# USB.net
KiCad netlist of a schematic drawn in Altium Designer
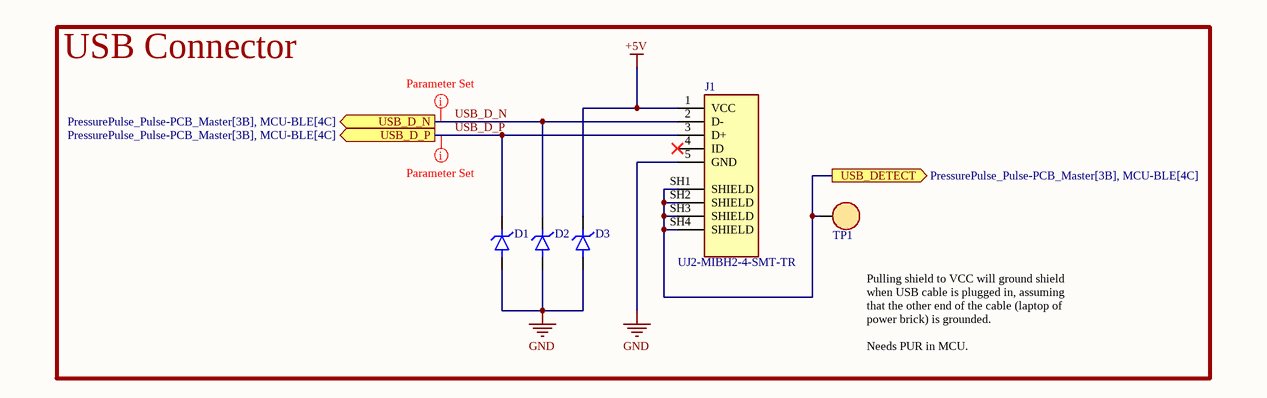
[diagram p0: USB.SchDoc]

(export (version "E")
  (design (tool "Eeschema 10.0.6"))
  (components
    (comp (ref "D1")
      (value "RCLAMP0521P.TCT")
      (footprint "PressurePulse:BDFN2C051V40")
      (description "25V Clamp 4A (8/20µs) Ipp Tvs Diode Surface Mount SLP1006P2")
      (fields (field (name "MFR") "BORN"))
      (libsource (lib "PressurePulse") (part "TVS DIODE"))
    )
    (comp (ref "D2")
      (value "RCLAMP0521P.TCT")
      (footprint "PressurePulse:BDFN2C051V40")
      (description "25V Clamp 4A (8/20µs) Ipp Tvs Diode Surface Mount SLP1006P2")
      (fields (field (name "MFR") "BORN"))
      (libsource (lib "PressurePulse") (part "TVS DIODE"))
    )
    (comp (ref "D3")
      (value "RCLAMP0521P.TCT")
      (footprint "PressurePulse:BDFN2C051V40")
      (description "25V Clamp 4A (8/20µs) Ipp Tvs Diode Surface Mount SLP1006P2")
      (fields (field (name "MFR") "BORN"))
      (libsource (lib "PressurePulse") (part "TVS DIODE"))
    )
    (comp (ref "J1")
      (value "UJ2-MIBH2-4-SMT-TR")
      (footprint "PressurePulse:USB MICRO JLC")
      (description "Micro B, USB 2.0, 1.8 A, Right Angle, Surface Mount (SMT), USB Receptacle")
      (fields (field (name "MFR") "CUI Devices"))
      (libsource (lib "PressurePulse") (part "Micro USB Port"))
    )
    (comp (ref "TP1")
      (value "RH-5019")
      (footprint "PressurePulse:TP - RH-5019")
      (fields (field (name "MFR") "ronghe"))
      (libsource (lib "PressurePulse") (part "TEST POINT"))
    )
  )
  (nets
    (net (code "1") (name "+5V") (class "Default")
      (node (ref "D3") (pin "K") (pinfunction "K_K") (pintype "passive"))
      (node (ref "J1") (pin "1") (pinfunction "VCC_1") (pintype "passive"))
    )
    (net (code "2") (name "/USB_DETECT") (class "Default")
      (node (ref "J1") (pin "SH1") (pinfunction "SHIELD_SH1") (pintype "passive"))
      (node (ref "J1") (pin "SH2") (pinfunction "SHIELD_SH2") (pintype "passive"))
      (node (ref "J1") (pin "SH3") (pinfunction "SHIELD_SH3") (pintype "passive"))
      (node (ref "J1") (pin "SH4") (pinfunction "SHIELD_SH4") (pintype "passive"))
      (node (ref "TP1") (pin "1") (pinfunction "1_1") (pintype "passive"))
    )
    (net (code "3") (name "/USB_D_N") (class "Default")
      (node (ref "D2") (pin "K") (pinfunction "K_K") (pintype "passive"))
      (node (ref "J1") (pin "2") (pinfunction "D-_2") (pintype "passive"))
    )
    (net (code "4") (name "/USB_D_P") (class "Default")
      (node (ref "D1") (pin "K") (pinfunction "K_K") (pintype "passive"))
      (node (ref "J1") (pin "3") (pinfunction "D+_3") (pintype "passive"))
    )
    (net (code "5") (name "GND") (class "Default")
      (node (ref "D1") (pin "A") (pinfunction "A_A") (pintype "passive"))
      (node (ref "D2") (pin "A") (pinfunction "A_A") (pintype "passive"))
      (node (ref "D3") (pin "A") (pinfunction "A_A") (pintype "passive"))
      (node (ref "J1") (pin "5") (pinfunction "GND_5") (pintype "passive"))
    )
    (net (code "6") (name "unconnected-(J1-ID-Pad4)") (class "Default")
      (node (ref "J1") (pin "4") (pinfunction "ID_4") (pintype "passive+no_connect"))
    )
  )
)
